# FTDI_AIO.net
KiCad netlist of a schematic drawn in EAGLE
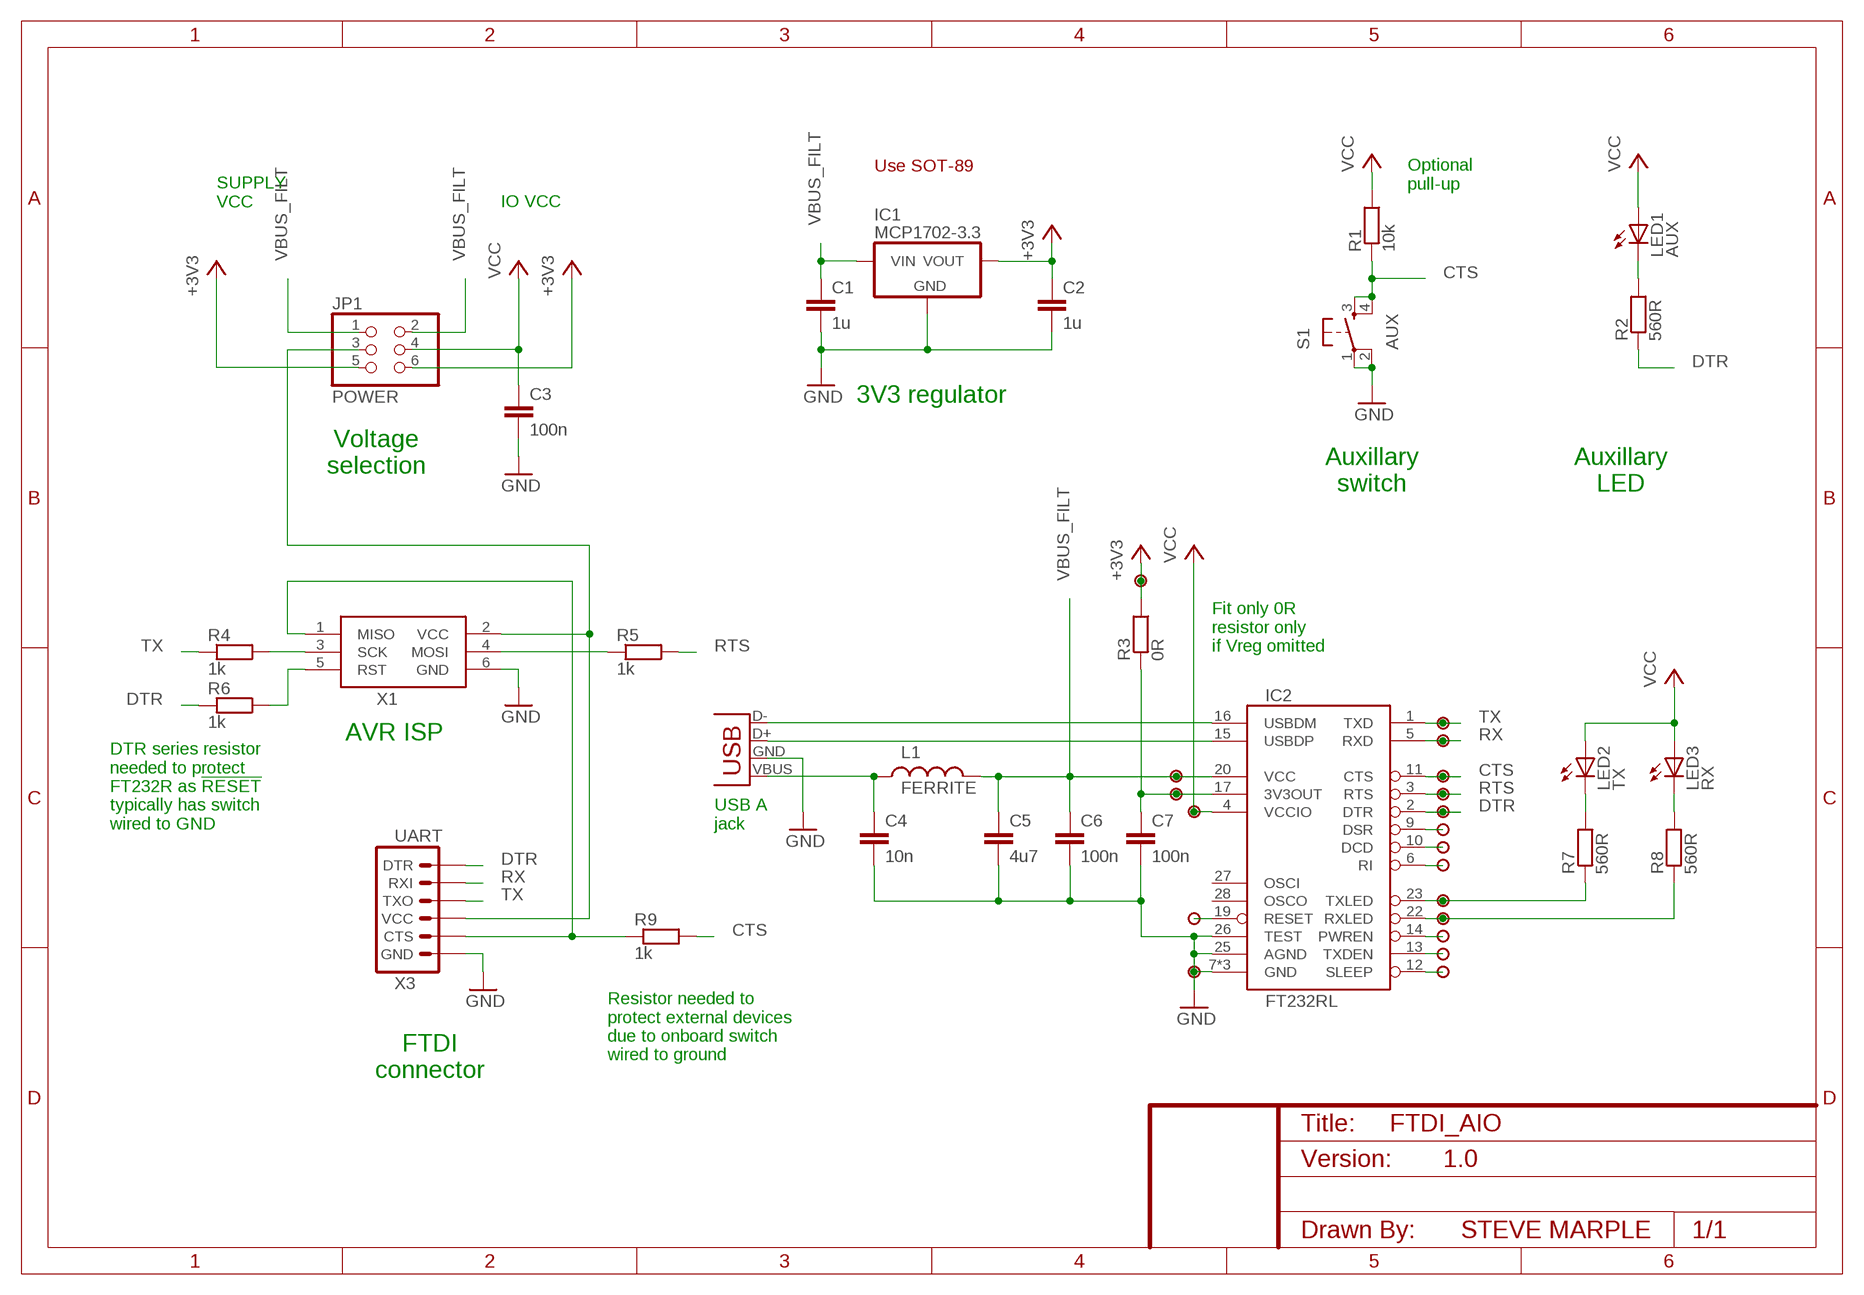
[diagram p0: schematic, sheet 1]

(export (version "E")
  (design (tool "Eeschema 10.0.6"))
  (components
    (comp (ref "C1")
      (value "1u")
      (footprint "eagle-import:1206-HAND")
      (libsource (lib "eagle-import") (part "C-EU1206-HAND"))
    )
    (comp (ref "C2")
      (value "1u")
      (footprint "eagle-import:1206-HAND")
      (libsource (lib "eagle-import") (part "C-EU1206-HAND"))
    )
    (comp (ref "C3")
      (value "100n")
      (footprint "eagle-import:1206-HAND")
      (libsource (lib "eagle-import") (part "C-EU1206-HAND"))
    )
    (comp (ref "C4")
      (value "10n")
      (footprint "eagle-import:1206-HAND")
      (libsource (lib "eagle-import") (part "C-EU1206-HAND"))
    )
    (comp (ref "C5")
      (value "4u7")
      (footprint "eagle-import:1206-HAND")
      (libsource (lib "eagle-import") (part "C-EU1206-HAND"))
    )
    (comp (ref "C6")
      (value "100n")
      (footprint "eagle-import:1206-HAND")
      (libsource (lib "eagle-import") (part "C-EU1206-HAND"))
    )
    (comp (ref "C7")
      (value "100n")
      (footprint "eagle-import:1206-HAND")
      (libsource (lib "eagle-import") (part "C-EU1206-HAND"))
    )
    (comp (ref "IC1")
      (value "MCP1702-3.3")
      (footprint "eagle-import:TO-92")
      (libsource (lib "eagle-import") (part "MCP1702"))
    )
    (comp (ref "IC2")
      (value "FT232RL")
      (footprint "eagle-import:SSOP28-HAND")
      (libsource (lib "eagle-import") (part "FT232RLSSOP-HAND"))
    )
    (comp (ref "JP1")
      (value "POWER")
      (footprint "eagle-import:2X03")
      (libsource (lib "eagle-import") (part "PINHD-2X3"))
    )
    (comp (ref "L1")
      (value "FERRITE")
      (footprint "eagle-import:0805-HAND")
      (libsource (lib "eagle-import") (part "INDUCTOR0805-HAND"))
    )
    (comp (ref "LED1")
      (value "AUX")
      (footprint "eagle-import:LED3MM")
      (libsource (lib "eagle-import") (part "LED3MM"))
    )
    (comp (ref "LED2")
      (value "TX")
      (footprint "eagle-import:LED3MM")
      (libsource (lib "eagle-import") (part "LED3MM"))
    )
    (comp (ref "LED3")
      (value "RX")
      (footprint "eagle-import:LED3MM")
      (libsource (lib "eagle-import") (part "LED3MM"))
    )
    (comp (ref "R1")
      (value "10k")
      (footprint "eagle-import:1206-HAND")
      (libsource (lib "eagle-import") (part "RESISTOR1206-HAND"))
    )
    (comp (ref "R2")
      (value "560R")
      (footprint "eagle-import:1206-HAND")
      (libsource (lib "eagle-import") (part "RESISTOR1206-HAND"))
    )
    (comp (ref "R3")
      (value "0R")
      (footprint "eagle-import:1206-HAND")
      (libsource (lib "eagle-import") (part "RESISTOR1206-HAND"))
    )
    (comp (ref "R4")
      (value "1k")
      (footprint "eagle-import:1206-HAND")
      (libsource (lib "eagle-import") (part "RESISTOR1206-HAND"))
    )
    (comp (ref "R5")
      (value "1k")
      (footprint "eagle-import:1206-HAND")
      (libsource (lib "eagle-import") (part "RESISTOR1206-HAND"))
    )
    (comp (ref "R6")
      (value "1k")
      (footprint "eagle-import:1206-HAND")
      (libsource (lib "eagle-import") (part "RESISTOR1206-HAND"))
    )
    (comp (ref "R7")
      (value "560R")
      (footprint "eagle-import:1206-HAND")
      (libsource (lib "eagle-import") (part "RESISTOR1206-HAND"))
    )
    (comp (ref "R8")
      (value "560R")
      (footprint "eagle-import:1206-HAND")
      (libsource (lib "eagle-import") (part "RESISTOR1206-HAND"))
    )
    (comp (ref "R9")
      (value "1k")
      (footprint "eagle-import:1206-HAND")
      (libsource (lib "eagle-import") (part "RESISTOR1206-HAND"))
    )
    (comp (ref "S1")
      (value "AUX")
      (footprint "eagle-import:TACTILE-PTH")
      (libsource (lib "eagle-import") (part "TAC_SWITCHPTH"))
    )
    (comp (ref "U$1")
      (value "PAD")
      (footprint "eagle-import:PAD")
      (libsource (lib "eagle-import") (part "PAD"))
    )
    (comp (ref "U$2")
      (value "PAD")
      (footprint "eagle-import:PAD")
      (libsource (lib "eagle-import") (part "PAD"))
    )
    (comp (ref "U$3")
      (value "PAD")
      (footprint "eagle-import:PAD")
      (libsource (lib "eagle-import") (part "PAD"))
    )
    (comp (ref "U$4")
      (value "PAD")
      (footprint "eagle-import:PAD")
      (libsource (lib "eagle-import") (part "PAD"))
    )
    (comp (ref "U$5")
      (value "PAD")
      (footprint "eagle-import:PAD")
      (libsource (lib "eagle-import") (part "PAD"))
    )
    (comp (ref "U$6")
      (value "PAD")
      (footprint "eagle-import:PAD")
      (libsource (lib "eagle-import") (part "PAD"))
    )
    (comp (ref "U$7")
      (value "PAD")
      (footprint "eagle-import:PAD")
      (libsource (lib "eagle-import") (part "PAD"))
    )
    (comp (ref "U$8")
      (value "PAD")
      (footprint "eagle-import:PAD")
      (libsource (lib "eagle-import") (part "PAD"))
    )
    (comp (ref "U$9")
      (value "PAD")
      (footprint "eagle-import:PAD")
      (libsource (lib "eagle-import") (part "PAD"))
    )
    (comp (ref "U$10")
      (value "PAD")
      (footprint "eagle-import:PAD")
      (libsource (lib "eagle-import") (part "PAD"))
    )
    (comp (ref "U$11")
      (value "PAD")
      (footprint "eagle-import:PAD")
      (libsource (lib "eagle-import") (part "PAD"))
    )
    (comp (ref "U$12")
      (value "PAD")
      (footprint "eagle-import:PAD")
      (libsource (lib "eagle-import") (part "PAD"))
    )
    (comp (ref "U$13")
      (value "PAD")
      (footprint "eagle-import:PAD")
      (libsource (lib "eagle-import") (part "PAD"))
    )
    (comp (ref "U$14")
      (value "PAD")
      (footprint "eagle-import:PAD")
      (libsource (lib "eagle-import") (part "PAD"))
    )
    (comp (ref "U$15")
      (value "PAD")
      (footprint "eagle-import:PAD")
      (libsource (lib "eagle-import") (part "PAD"))
    )
    (comp (ref "U$16")
      (value "PAD")
      (footprint "eagle-import:PAD")
      (libsource (lib "eagle-import") (part "PAD"))
    )
    (comp (ref "U$17")
      (value "PAD")
      (footprint "eagle-import:PAD")
      (libsource (lib "eagle-import") (part "PAD"))
    )
    (comp (ref "U$18")
      (value "PAD")
      (footprint "eagle-import:PAD")
      (libsource (lib "eagle-import") (part "PAD"))
    )
    (comp (ref "U$19")
      (value "PAD")
      (footprint "eagle-import:PAD")
      (libsource (lib "eagle-import") (part "PAD"))
    )
    (comp (ref "X1")
      (value "ISP")
      (footprint "eagle-import:CONN-HARTING-ML6")
      (libsource (lib "eagle-import") (part "AVRISP-HEADER-6-SHROUDED"))
    )
    (comp (ref "X2")
      (value "USB-A-H")
      (footprint "eagle-import:USB-A-H")
      (libsource (lib "eagle-import") (part "USB-A-H"))
    )
    (comp (ref "X3")
      (value "UART")
      (footprint "eagle-import:1X06")
      (libsource (lib "eagle-import") (part "ARDUINO_SERIAL_PROGRAMPTH"))
    )
  )
  (nets
    (net (code "1") (name "+3V3") (class "Default")
      (node (ref "C2") (pin "1") (pinfunction "1_1") (pintype "passive"))
      (node (ref "IC1") (pin "3") (pinfunction "VOUT_3") (pintype "passive"))
      (node (ref "JP1") (pin "5") (pinfunction "5_5") (pintype "passive"))
      (node (ref "JP1") (pin "6") (pinfunction "6_6") (pintype "passive"))
      (node (ref "R3") (pin "2") (pinfunction "2_2") (pintype "passive"))
      (node (ref "U$1") (pin "1") (pinfunction "1_1") (pintype "bidirectional"))
    )
    (net (code "2") (name "/CTS") (class "Default")
      (node (ref "IC2") (pin "11") (pinfunction "CTS_11") (pintype "input"))
      (node (ref "R1") (pin "1") (pinfunction "1_1") (pintype "passive"))
      (node (ref "R9") (pin "2") (pinfunction "2_2") (pintype "passive"))
      (node (ref "S1") (pin "3") (pinfunction "3_3") (pintype "passive"))
      (node (ref "S1") (pin "4") (pinfunction "4_4") (pintype "passive"))
      (node (ref "U$5") (pin "1") (pinfunction "1_1") (pintype "bidirectional"))
    )
    (net (code "3") (name "/DTR") (class "Default")
      (node (ref "IC2") (pin "2") (pinfunction "DTR_2") (pintype "output"))
      (node (ref "R2") (pin "1") (pinfunction "1_1") (pintype "passive"))
      (node (ref "R6") (pin "1") (pinfunction "1_1") (pintype "passive"))
      (node (ref "U$9") (pin "1") (pinfunction "1_1") (pintype "bidirectional"))
      (node (ref "X3") (pin "1") (pinfunction "DTR_1") (pintype "passive"))
    )
    (net (code "4") (name "/RTS") (class "Default")
      (node (ref "IC2") (pin "3") (pinfunction "RTS_3") (pintype "output"))
      (node (ref "R5") (pin "2") (pinfunction "2_2") (pintype "passive"))
      (node (ref "U$7") (pin "1") (pinfunction "1_1") (pintype "bidirectional"))
    )
    (net (code "5") (name "/RX") (class "Default")
      (node (ref "IC2") (pin "5") (pinfunction "RXD_5") (pintype "input"))
      (node (ref "U$3") (pin "1") (pinfunction "1_1") (pintype "bidirectional"))
      (node (ref "X3") (pin "2") (pinfunction "RXI_2") (pintype "passive"))
    )
    (net (code "6") (name "/TX") (class "Default")
      (node (ref "IC2") (pin "1") (pinfunction "TXD_1") (pintype "output"))
      (node (ref "R4") (pin "1") (pinfunction "1_1") (pintype "passive"))
      (node (ref "U$2") (pin "1") (pinfunction "1_1") (pintype "bidirectional"))
      (node (ref "X3") (pin "3") (pinfunction "TXO_3") (pintype "passive"))
    )
    (net (code "7") (name "/VBUS_FILT") (class "Default")
      (node (ref "C1") (pin "1") (pinfunction "1_1") (pintype "passive"))
      (node (ref "C5") (pin "1") (pinfunction "1_1") (pintype "passive"))
      (node (ref "C6") (pin "1") (pinfunction "1_1") (pintype "passive"))
      (node (ref "IC1") (pin "2") (pinfunction "VIN_2") (pintype "input"))
      (node (ref "IC2") (pin "20") (pinfunction "VCC_20") (pintype "power_in"))
      (node (ref "JP1") (pin "1") (pinfunction "1_1") (pintype "passive"))
      (node (ref "JP1") (pin "2") (pinfunction "2_2") (pintype "passive"))
      (node (ref "L1") (pin "2") (pinfunction "2_2") (pintype "passive"))
      (node (ref "U$4") (pin "1") (pinfunction "1_1") (pintype "bidirectional"))
    )
    (net (code "8") (name "GND") (class "Default")
      (node (ref "C1") (pin "2") (pinfunction "2_2") (pintype "passive"))
      (node (ref "C2") (pin "2") (pinfunction "2_2") (pintype "passive"))
      (node (ref "C3") (pin "2") (pinfunction "2_2") (pintype "passive"))
      (node (ref "C4") (pin "2") (pinfunction "2_2") (pintype "passive"))
      (node (ref "C5") (pin "2") (pinfunction "2_2") (pintype "passive"))
      (node (ref "C6") (pin "2") (pinfunction "2_2") (pintype "passive"))
      (node (ref "C7") (pin "2") (pinfunction "2_2") (pintype "passive"))
      (node (ref "IC1") (pin "1") (pinfunction "GND_1") (pintype "passive"))
      (node (ref "IC2") (pin "18") (pinfunction "GND_18") (pintype "power_in"))
      (node (ref "IC2") (pin "21") (pinfunction "GND_21") (pintype "power_in"))
      (node (ref "IC2") (pin "25") (pinfunction "AGND_25") (pintype "power_in"))
      (node (ref "IC2") (pin "26") (pinfunction "TEST_26") (pintype "input"))
      (node (ref "IC2") (pin "7") (pinfunction "GND_7") (pintype "power_in"))
      (node (ref "S1") (pin "1") (pinfunction "1_1") (pintype "passive"))
      (node (ref "S1") (pin "2") (pinfunction "2_2") (pintype "passive"))
      (node (ref "U$18") (pin "1") (pinfunction "1_1") (pintype "bidirectional"))
      (node (ref "X1") (pin "6") (pinfunction "GND_6") (pintype "power_in"))
      (node (ref "X2") (pin "GND") (pinfunction "VBUS_GND") (pintype "bidirectional"))
      (node (ref "X3") (pin "6") (pinfunction "GND_6") (pintype "passive"))
    )
    (net (code "9") (name "Net-(IC2-3V3OUT)") (class "Default")
      (node (ref "C7") (pin "1") (pinfunction "1_1") (pintype "passive"))
      (node (ref "IC2") (pin "17") (pinfunction "3V3OUT_17") (pintype "output"))
      (node (ref "R3") (pin "1") (pinfunction "1_1") (pintype "passive"))
      (node (ref "U$6") (pin "1") (pinfunction "1_1") (pintype "bidirectional"))
    )
    (net (code "10") (name "Net-(IC2-DCD)") (class "Default")
      (node (ref "IC2") (pin "10") (pinfunction "DCD_10") (pintype "input"))
      (node (ref "U$11") (pin "1") (pinfunction "1_1") (pintype "bidirectional"))
    )
    (net (code "11") (name "Net-(IC2-DSR)") (class "Default")
      (node (ref "IC2") (pin "9") (pinfunction "DSR_9") (pintype "input"))
      (node (ref "U$10") (pin "1") (pinfunction "1_1") (pintype "bidirectional"))
    )
    (net (code "12") (name "Net-(IC2-PWREN)") (class "Default")
      (node (ref "IC2") (pin "14") (pinfunction "PWREN_14") (pintype "input"))
      (node (ref "U$16") (pin "1") (pinfunction "1_1") (pintype "bidirectional"))
    )
    (net (code "13") (name "Net-(IC2-RESET)") (class "Default")
      (node (ref "IC2") (pin "19") (pinfunction "RESET_19") (pintype "input"))
      (node (ref "U$14") (pin "1") (pinfunction "1_1") (pintype "bidirectional"))
    )
    (net (code "14") (name "Net-(IC2-RI)") (class "Default")
      (node (ref "IC2") (pin "6") (pinfunction "RI_6") (pintype "input"))
      (node (ref "U$12") (pin "1") (pinfunction "1_1") (pintype "bidirectional"))
    )
    (net (code "15") (name "Net-(IC2-RXLED)") (class "Default")
      (node (ref "IC2") (pin "22") (pinfunction "RXLED_22") (pintype "input"))
      (node (ref "R8") (pin "1") (pinfunction "1_1") (pintype "passive"))
      (node (ref "U$15") (pin "1") (pinfunction "1_1") (pintype "bidirectional"))
    )
    (net (code "16") (name "Net-(IC2-SLEEP)") (class "Default")
      (node (ref "IC2") (pin "12") (pinfunction "SLEEP_12") (pintype "input"))
      (node (ref "U$19") (pin "1") (pinfunction "1_1") (pintype "bidirectional"))
    )
    (net (code "17") (name "Net-(IC2-TXDEN)") (class "Default")
      (node (ref "IC2") (pin "13") (pinfunction "TXDEN_13") (pintype "input"))
      (node (ref "U$17") (pin "1") (pinfunction "1_1") (pintype "bidirectional"))
    )
    (net (code "18") (name "Net-(IC2-TXLED)") (class "Default")
      (node (ref "IC2") (pin "23") (pinfunction "TXLED_23") (pintype "input"))
      (node (ref "R7") (pin "1") (pinfunction "1_1") (pintype "passive"))
      (node (ref "U$13") (pin "1") (pinfunction "1_1") (pintype "bidirectional"))
    )
    (net (code "19") (name "Net-(IC2-USBDM)") (class "Default")
      (node (ref "IC2") (pin "16") (pinfunction "USBDM_16") (pintype "bidirectional"))
      (node (ref "X2") (pin "D-") (pinfunction "D+_D-") (pintype "bidirectional"))
    )
    (net (code "20") (name "Net-(IC2-USBDP)") (class "Default")
      (node (ref "IC2") (pin "15") (pinfunction "USBDP_15") (pintype "bidirectional"))
      (node (ref "X2") (pin "D+") (pinfunction "D-_D+") (pintype "bidirectional"))
    )
    (net (code "21") (name "Net-(LED1-C)") (class "Default")
      (node (ref "LED1") (pin "K") (pinfunction "C_K") (pintype "passive"))
      (node (ref "R2") (pin "2") (pinfunction "2_2") (pintype "passive"))
    )
    (net (code "22") (name "Net-(LED2-C)") (class "Default")
      (node (ref "LED2") (pin "K") (pinfunction "C_K") (pintype "passive"))
      (node (ref "R7") (pin "2") (pinfunction "2_2") (pintype "passive"))
    )
    (net (code "23") (name "Net-(LED3-C)") (class "Default")
      (node (ref "LED3") (pin "K") (pinfunction "C_K") (pintype "passive"))
      (node (ref "R8") (pin "2") (pinfunction "2_2") (pintype "passive"))
    )
    (net (code "24") (name "Net-(X1-MISO)") (class "Default")
      (node (ref "R9") (pin "1") (pinfunction "1_1") (pintype "passive"))
      (node (ref "X1") (pin "1") (pinfunction "MISO_1") (pintype "input"))
      (node (ref "X3") (pin "5") (pinfunction "CTS_5") (pintype "passive"))
    )
    (net (code "25") (name "Net-(X1-MOSI)") (class "Default")
      (node (ref "R5") (pin "1") (pinfunction "1_1") (pintype "passive"))
      (node (ref "X1") (pin "4") (pinfunction "MOSI_4") (pintype "output"))
    )
    (net (code "26") (name "Net-(X1-RST)") (class "Default")
      (node (ref "R6") (pin "2") (pinfunction "2_2") (pintype "passive"))
      (node (ref "X1") (pin "5") (pinfunction "RST_5") (pintype "output"))
    )
    (net (code "27") (name "Net-(X1-SCK)") (class "Default")
      (node (ref "R4") (pin "2") (pinfunction "2_2") (pintype "passive"))
      (node (ref "X1") (pin "3") (pinfunction "SCK_3") (pintype "output"))
    )
    (net (code "28") (name "Net-(X1-VCC)") (class "Default")
      (node (ref "JP1") (pin "3") (pinfunction "3_3") (pintype "passive"))
      (node (ref "X1") (pin "2") (pinfunction "VCC_2") (pintype "power_in"))
      (node (ref "X3") (pin "4") (pinfunction "VCC_4") (pintype "passive"))
    )
    (net (code "29") (name "Net-(X2-GND)") (class "Default")
      (node (ref "C4") (pin "1") (pinfunction "1_1") (pintype "passive"))
      (node (ref "L1") (pin "1") (pinfunction "1_1") (pintype "passive"))
      (node (ref "X2") (pin "VBUS") (pinfunction "GND_VBUS") (pintype "bidirectional"))
    )
    (net (code "30") (name "VCC") (class "Default")
      (node (ref "C3") (pin "1") (pinfunction "1_1") (pintype "passive"))
      (node (ref "IC2") (pin "4") (pinfunction "VCCIO_4") (pintype "power_in"))
      (node (ref "JP1") (pin "4") (pinfunction "4_4") (pintype "passive"))
      (node (ref "LED1") (pin "A") (pinfunction "A_A") (pintype "passive"))
      (node (ref "LED2") (pin "A") (pinfunction "A_A") (pintype "passive"))
      (node (ref "LED3") (pin "A") (pinfunction "A_A") (pintype "passive"))
      (node (ref "R1") (pin "2") (pinfunction "2_2") (pintype "passive"))
      (node (ref "U$8") (pin "1") (pinfunction "1_1") (pintype "bidirectional"))
    )
    (net (code "31") (name "unconnected-(IC2-OSCI-Pad27)") (class "Default")
      (node (ref "IC2") (pin "27") (pinfunction "OSCI_27") (pintype "input"))
    )
    (net (code "32") (name "unconnected-(IC2-OSCO-Pad28)") (class "Default")
      (node (ref "IC2") (pin "28") (pinfunction "OSCO_28") (pintype "output"))
    )
  )
)
